# Sheet_1_2024-11-08.net
KiCad netlist of a schematic drawn in Altium Designer
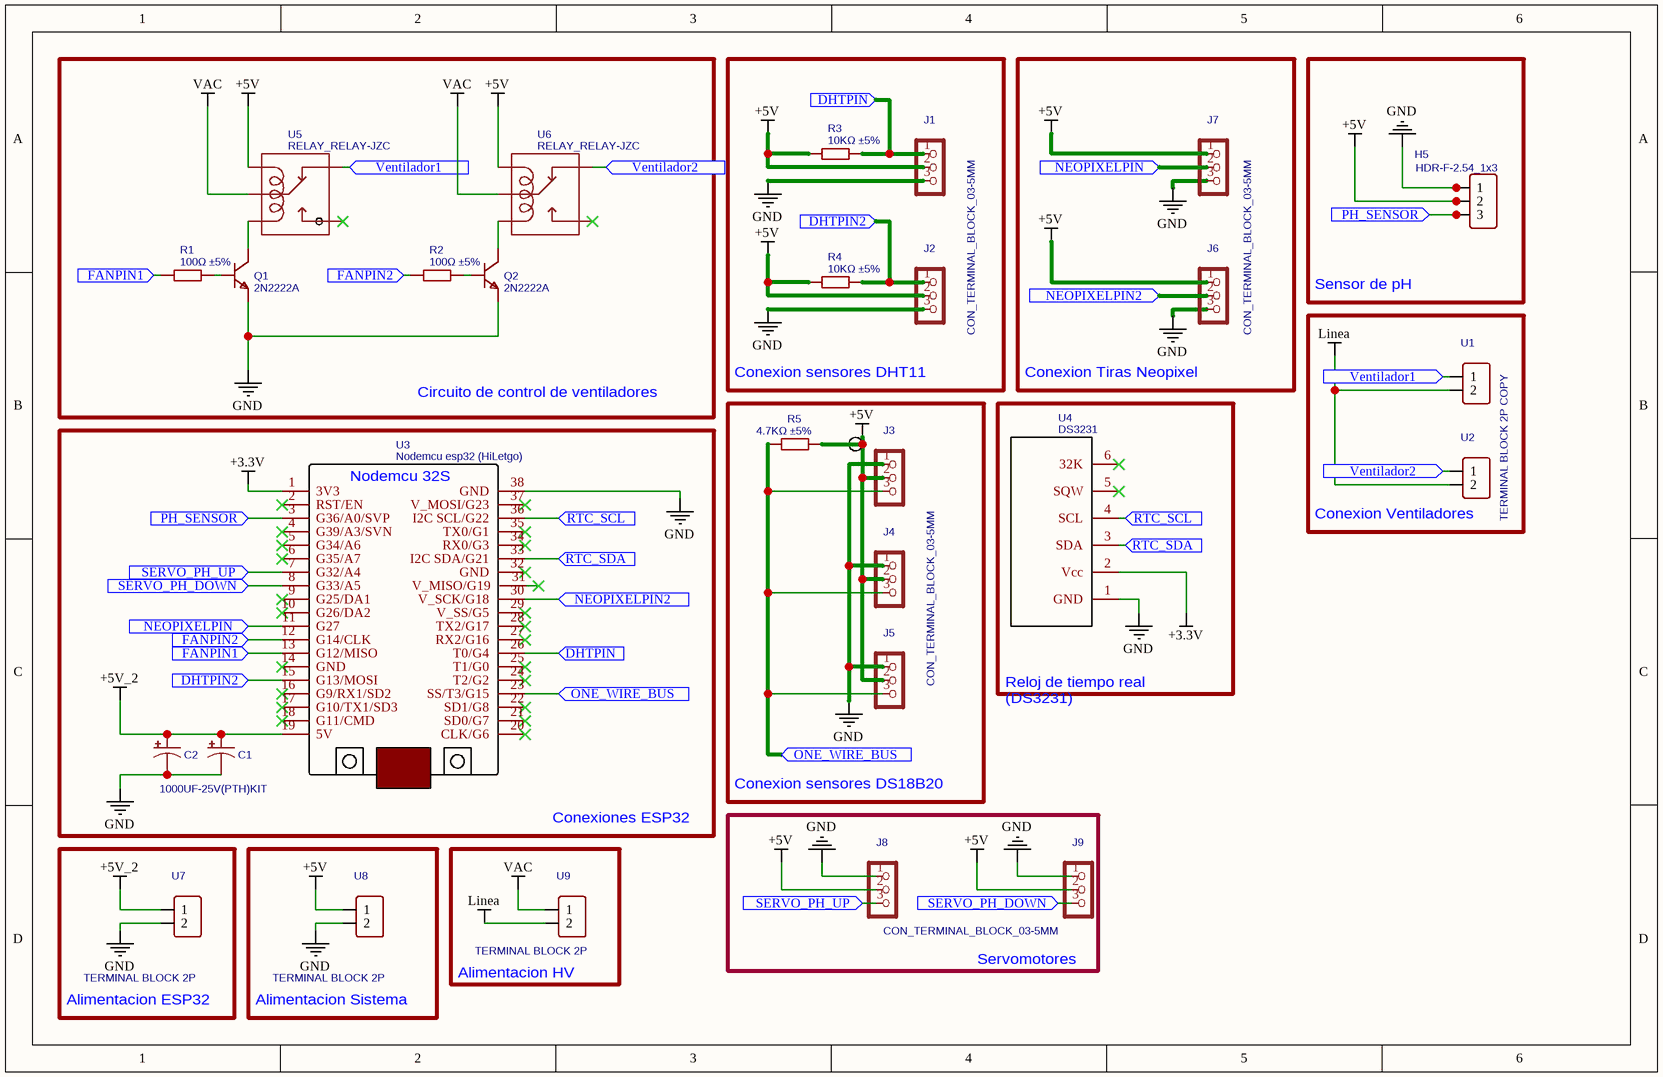
[diagram p0: Sheet_1_2024-11-08.schdoc]

(export (version "E")
  (design (tool "Eeschema 10.0.6"))
  (components
    (comp (ref "C1")
      (value "1000UF-25V(PTH)KIT")
      (description "CAP-08070")
      (fields (field (name "CONTRIBUTOR") "SparkFun"))
      (libsource (lib "altium-import") (part "root_0_1000UF-25V(PTH)KIT_"))
    )
    (comp (ref "C2")
      (value "1000UF-25V(PTH)KIT")
      (description "CAP-08070")
      (fields (field (name "CONTRIBUTOR") "SparkFun"))
      (libsource (lib "altium-import") (part "root_0_1000UF-25V(PTH)KIT_"))
    )
    (comp (ref "H5")
      (value "HDR-F-2.54_1x3")
      (fields (field (name "BOM_SUPPLIER PART") "C146690") (field (name "CONTRIBUTOR") "LCEDA_Lib"))
      (libsource (lib "altium-import") (part "root_0_HDR-F-2.54_1x3_"))
    )
    (comp (ref "J1")
      (value "CON_TERMINAL_BLOCK_03-5MM")
      (description "3 poles, wire to board connector")
      (fields (field (name "CONTRIBUTOR") "DangerousPrototype"))
      (libsource (lib "altium-import") (part "root_0_CON_TERMINAL_BLOCK_03-5MM_"))
    )
    (comp (ref "J2")
      (value "CON_TERMINAL_BLOCK_03-5MM")
      (description "3 poles, wire to board connector")
      (fields (field (name "CONTRIBUTOR") "DangerousPrototype"))
      (libsource (lib "altium-import") (part "root_0_CON_TERMINAL_BLOCK_03-5MM_"))
    )
    (comp (ref "J3")
      (value "CON_TERMINAL_BLOCK_03-5MM")
      (description "3 poles, wire to board connector")
      (fields (field (name "CONTRIBUTOR") "DangerousPrototype"))
      (libsource (lib "altium-import") (part "root_0_CON_TERMINAL_BLOCK_03-5MM_"))
    )
    (comp (ref "J4")
      (value "CON_TERMINAL_BLOCK_03-5MM")
      (description "3 poles, wire to board connector")
      (fields (field (name "CONTRIBUTOR") "DangerousPrototype"))
      (libsource (lib "altium-import") (part "root_0_CON_TERMINAL_BLOCK_03-5MM_"))
    )
    (comp (ref "J5")
      (value "CON_TERMINAL_BLOCK_03-5MM")
      (description "3 poles, wire to board connector")
      (fields (field (name "CONTRIBUTOR") "DangerousPrototype"))
      (libsource (lib "altium-import") (part "root_0_CON_TERMINAL_BLOCK_03-5MM_"))
    )
    (comp (ref "J6")
      (value "CON_TERMINAL_BLOCK_03-5MM")
      (description "3 poles, wire to board connector")
      (fields (field (name "CONTRIBUTOR") "DangerousPrototype"))
      (libsource (lib "altium-import") (part "root_0_CON_TERMINAL_BLOCK_03-5MM_"))
    )
    (comp (ref "J7")
      (value "CON_TERMINAL_BLOCK_03-5MM")
      (description "3 poles, wire to board connector")
      (fields (field (name "CONTRIBUTOR") "DangerousPrototype"))
      (libsource (lib "altium-import") (part "root_0_CON_TERMINAL_BLOCK_03-5MM_"))
    )
    (comp (ref "J8")
      (value "CON_TERMINAL_BLOCK_03-5MM")
      (description "3 poles, wire to board connector")
      (fields (field (name "CONTRIBUTOR") "DangerousPrototype"))
      (libsource (lib "altium-import") (part "root_0_CON_TERMINAL_BLOCK_03-5MM_"))
    )
    (comp (ref "J9")
      (value "CON_TERMINAL_BLOCK_03-5MM")
      (description "3 poles, wire to board connector")
      (fields (field (name "CONTRIBUTOR") "DangerousPrototype"))
      (libsource (lib "altium-import") (part "root_0_CON_TERMINAL_BLOCK_03-5MM_"))
    )
    (comp (ref "Q1")
      (value "2N2222A")
      (fields (field (name "BOM_SUPPLIER PART") "C358533") (field (name "CONTRIBUTOR") "som3a elshayeb"))
      (libsource (lib "altium-import") (part "root_0_2N2222A_"))
    )
    (comp (ref "Q2")
      (value "2N2222A")
      (fields (field (name "BOM_SUPPLIER PART") "C358533") (field (name "CONTRIBUTOR") "som3a elshayeb"))
      (libsource (lib "altium-import") (part "root_0_2N2222A_"))
    )
    (comp (ref "R1")
      (value "100Ω ±5%")
      (fields
        (field (name "BOM_SUPPLIER PART") "C123392")
        (field (name "BOM_MANUFACTURER PART") "MF58 103J3470")
        (field (name "CONTRIBUTOR") "Evgeniy_ANP")
      )
      (libsource (lib "altium-import") (part "root_0_100Ω ±5%_"))
    )
    (comp (ref "R2")
      (value "100Ω ±5%")
      (fields
        (field (name "BOM_SUPPLIER PART") "C123392")
        (field (name "BOM_MANUFACTURER PART") "MF58 103J3470")
        (field (name "CONTRIBUTOR") "Evgeniy_ANP")
      )
      (libsource (lib "altium-import") (part "root_0_100Ω ±5%_"))
    )
    (comp (ref "R3")
      (value "10KΩ ±5%")
      (fields
        (field (name "BOM_SUPPLIER PART") "C123392")
        (field (name "BOM_MANUFACTURER PART") "MF58 103J3470")
        (field (name "CONTRIBUTOR") "Evgeniy_ANP")
      )
      (libsource (lib "altium-import") (part "root_0_10KΩ ±5%_"))
    )
    (comp (ref "R4")
      (value "10KΩ ±5%")
      (fields
        (field (name "BOM_SUPPLIER PART") "C123392")
        (field (name "BOM_MANUFACTURER PART") "MF58 103J3470")
        (field (name "CONTRIBUTOR") "Evgeniy_ANP")
      )
      (libsource (lib "altium-import") (part "root_0_10KΩ ±5%_"))
    )
    (comp (ref "R5")
      (value "4.7KΩ ±5%")
      (fields
        (field (name "BOM_SUPPLIER PART") "C123392")
        (field (name "BOM_MANUFACTURER PART") "MF58 103J3470")
        (field (name "CONTRIBUTOR") "Evgeniy_ANP")
      )
      (libsource (lib "altium-import") (part "root_0_4.7KΩ ±5%_"))
    )
    (comp (ref "U1")
      (value "TERMINAL BLOCK 2P COPY")
      (fields (field (name "CONTRIBUTOR") "malakathushan"))
      (libsource (lib "altium-import") (part "root_0_TERMINAL BLOCK 2P COPY_"))
    )
    (comp (ref "U2")
      (value "TERMINAL BLOCK 2P COPY")
      (fields (field (name "CONTRIBUTOR") "malakathushan"))
      (libsource (lib "altium-import") (part "root_0_TERMINAL BLOCK 2P COPY_"))
    )
    (comp (ref "U3")
      (value "Nodemcu esp32 (HiLetgo)")
      (fields (field (name "CONTRIBUTOR") "j_dalrym2"))
      (libsource (lib "altium-import") (part "root_0_Nodemcu esp32 (HiLetgo)_"))
    )
    (comp (ref "U4")
      (value "DS3231")
      (fields (field (name "CONTRIBUTOR") "mwneal2014"))
      (libsource (lib "altium-import") (part "root_1_DS3231_"))
    )
    (comp (ref "U5")
      (value "RELAY_RELAY-JZC")
      (libsource (lib "altium-import") (part "root_0_RELAY_RELAY-JZC_"))
    )
    (comp (ref "U6")
      (value "RELAY_RELAY-JZC")
      (libsource (lib "altium-import") (part "root_0_RELAY_RELAY-JZC_"))
    )
    (comp (ref "U7")
      (value "TERMINAL BLOCK 2P")
      (fields (field (name "CONTRIBUTOR") "malakathushan"))
      (libsource (lib "altium-import") (part "root_0_TERMINAL BLOCK 2P_"))
    )
    (comp (ref "U8")
      (value "TERMINAL BLOCK 2P")
      (fields (field (name "CONTRIBUTOR") "malakathushan"))
      (libsource (lib "altium-import") (part "root_0_TERMINAL BLOCK 2P_"))
    )
    (comp (ref "U9")
      (value "TERMINAL BLOCK 2P")
      (fields (field (name "CONTRIBUTOR") "malakathushan"))
      (libsource (lib "altium-import") (part "root_0_TERMINAL BLOCK 2P_"))
    )
  )
  (nets
    (net (code "1") (name "+3.3V") (class "Default")
      (node (ref "U3") (pin "1") (pinfunction "3V3_1") (pintype "passive"))
      (node (ref "U4") (pin "2") (pinfunction "Vcc_2") (pintype "passive"))
    )
    (net (code "2") (name "+5V") (class "Default")
      (node (ref "H5") (pin "2") (pinfunction "2_2") (pintype "passive"))
      (node (ref "J1") (pin "2") (pinfunction "2_2") (pintype "passive"))
      (node (ref "J2") (pin "2") (pinfunction "2_2") (pintype "passive"))
      (node (ref "J3") (pin "2") (pinfunction "2_2") (pintype "passive"))
      (node (ref "J4") (pin "2") (pinfunction "2_2") (pintype "passive"))
      (node (ref "J5") (pin "2") (pinfunction "2_2") (pintype "passive"))
      (node (ref "J6") (pin "1") (pinfunction "1_1") (pintype "passive"))
      (node (ref "J7") (pin "1") (pinfunction "1_1") (pintype "passive"))
      (node (ref "J8") (pin "2") (pinfunction "2_2") (pintype "passive"))
      (node (ref "J9") (pin "2") (pinfunction "2_2") (pintype "passive"))
      (node (ref "R3") (pin "1") (pinfunction "1_1") (pintype "passive"))
      (node (ref "R4") (pin "1") (pinfunction "1_1") (pintype "passive"))
      (node (ref "R5") (pin "2") (pinfunction "2_2") (pintype "passive"))
      (node (ref "U5") (pin "1") (pinfunction "COIL1_1") (pintype "passive"))
      (node (ref "U6") (pin "1") (pinfunction "COIL1_1") (pintype "passive"))
      (node (ref "U8") (pin "1") (pinfunction "1_1") (pintype "passive"))
    )
    (net (code "3") (name "+5V_2") (class "Default")
      (node (ref "C1") (pin "+") (pinfunction "+_+") (pintype "passive"))
      (node (ref "C2") (pin "+") (pinfunction "+_+") (pintype "passive"))
      (node (ref "U3") (pin "19") (pinfunction "5V_19") (pintype "passive"))
      (node (ref "U7") (pin "1") (pinfunction "1_1") (pintype "passive"))
    )
    (net (code "4") (name "/DHTPIN") (class "Default")
      (node (ref "J1") (pin "1") (pinfunction "1_1") (pintype "passive"))
      (node (ref "R3") (pin "2") (pinfunction "2_2") (pintype "passive"))
      (node (ref "U3") (pin "26") (pinfunction "T0/G4_26") (pintype "passive"))
    )
    (net (code "5") (name "/DHTPIN2") (class "Default")
      (node (ref "J2") (pin "1") (pinfunction "1_1") (pintype "passive"))
      (node (ref "R4") (pin "2") (pinfunction "2_2") (pintype "passive"))
      (node (ref "U3") (pin "15") (pinfunction "G13/MOSI_15") (pintype "passive"))
    )
    (net (code "6") (name "/FANPIN1") (class "Default")
      (node (ref "R1") (pin "1") (pinfunction "1_1") (pintype "passive"))
      (node (ref "U3") (pin "13") (pinfunction "G12/MISO_13") (pintype "passive"))
    )
    (net (code "7") (name "/FANPIN2") (class "Default")
      (node (ref "R2") (pin "1") (pinfunction "1_1") (pintype "passive"))
      (node (ref "U3") (pin "12") (pinfunction "G14/CLK_12") (pintype "passive"))
    )
    (net (code "8") (name "/NEOPIXELPIN") (class "Default")
      (node (ref "J7") (pin "2") (pinfunction "2_2") (pintype "passive"))
      (node (ref "U3") (pin "11") (pinfunction "G27_11") (pintype "passive"))
    )
    (net (code "9") (name "/NEOPIXELPIN2") (class "Default")
      (node (ref "J6") (pin "2") (pinfunction "2_2") (pintype "passive"))
      (node (ref "U3") (pin "30") (pinfunction "V_SCK/G18_30") (pintype "passive"))
    )
    (net (code "10") (name "/ONE_WIRE_BUS") (class "Default")
      (node (ref "J3") (pin "3") (pinfunction "3_3") (pintype "passive"))
      (node (ref "J4") (pin "3") (pinfunction "3_3") (pintype "passive"))
      (node (ref "J5") (pin "3") (pinfunction "3_3") (pintype "passive"))
      (node (ref "R5") (pin "1") (pinfunction "1_1") (pintype "passive"))
      (node (ref "U3") (pin "23") (pinfunction "SS/T3/G15_23") (pintype "passive"))
    )
    (net (code "11") (name "/PH_SENSOR") (class "Default")
      (node (ref "H5") (pin "3") (pinfunction "3_3") (pintype "passive"))
      (node (ref "U3") (pin "3") (pinfunction "G36/A0/SVP_3") (pintype "passive"))
    )
    (net (code "12") (name "/RTC_SCL") (class "Default")
      (node (ref "U3") (pin "36") (pinfunction "I2C_SCL/G22_36") (pintype "passive"))
      (node (ref "U4") (pin "4") (pinfunction "SCL_4") (pintype "passive"))
    )
    (net (code "13") (name "/RTC_SDA") (class "Default")
      (node (ref "U3") (pin "33") (pinfunction "I2C_SDA/G21_33") (pintype "passive"))
      (node (ref "U4") (pin "3") (pinfunction "SDA_3") (pintype "passive"))
    )
    (net (code "14") (name "/SERVO_PH_DOWN") (class "Default")
      (node (ref "J9") (pin "3") (pinfunction "3_3") (pintype "passive"))
      (node (ref "U3") (pin "8") (pinfunction "G33/A5_8") (pintype "passive"))
    )
    (net (code "15") (name "/SERVO_PH_UP") (class "Default")
      (node (ref "J8") (pin "3") (pinfunction "3_3") (pintype "passive"))
      (node (ref "U3") (pin "7") (pinfunction "G32/A4_7") (pintype "passive"))
    )
    (net (code "16") (name "/Ventilador1") (class "Default")
      (node (ref "U1") (pin "1") (pinfunction "1_1") (pintype "passive"))
      (node (ref "U5") (pin "14") (pinfunction "NC_14") (pintype "passive"))
    )
    (net (code "17") (name "/Ventilador2") (class "Default")
      (node (ref "U2") (pin "1") (pinfunction "1_1") (pintype "passive"))
      (node (ref "U6") (pin "14") (pinfunction "NC_14") (pintype "passive"))
    )
    (net (code "18") (name "GND") (class "Default")
      (node (ref "C1") (pin "-") (pinfunction "-_-") (pintype "passive"))
      (node (ref "C2") (pin "-") (pinfunction "-_-") (pintype "passive"))
      (node (ref "H5") (pin "1") (pinfunction "1_1") (pintype "passive"))
      (node (ref "J1") (pin "3") (pinfunction "3_3") (pintype "passive"))
      (node (ref "J2") (pin "3") (pinfunction "3_3") (pintype "passive"))
      (node (ref "J3") (pin "1") (pinfunction "1_1") (pintype "passive"))
      (node (ref "J4") (pin "1") (pinfunction "1_1") (pintype "passive"))
      (node (ref "J5") (pin "1") (pinfunction "1_1") (pintype "passive"))
      (node (ref "J6") (pin "3") (pinfunction "3_3") (pintype "passive"))
      (node (ref "J7") (pin "3") (pinfunction "3_3") (pintype "passive"))
      (node (ref "J8") (pin "1") (pinfunction "1_1") (pintype "passive"))
      (node (ref "J9") (pin "1") (pinfunction "1_1") (pintype "passive"))
      (node (ref "Q1") (pin "3") (pinfunction "E_3") (pintype "passive"))
      (node (ref "Q2") (pin "3") (pinfunction "E_3") (pintype "passive"))
      (node (ref "U3") (pin "38") (pinfunction "GND_38") (pintype "passive"))
      (node (ref "U4") (pin "1") (pinfunction "GND_1") (pintype "passive"))
      (node (ref "U7") (pin "2") (pinfunction "2_2") (pintype "passive"))
      (node (ref "U8") (pin "2") (pinfunction "2_2") (pintype "passive"))
    )
    (net (code "19") (name "Linea") (class "Default")
      (node (ref "U1") (pin "2") (pinfunction "2_2") (pintype "passive"))
      (node (ref "U2") (pin "2") (pinfunction "2_2") (pintype "passive"))
      (node (ref "U9") (pin "2") (pinfunction "2_2") (pintype "passive"))
    )
    (net (code "20") (name "Net-(Q1-B)") (class "Default")
      (node (ref "Q1") (pin "2") (pinfunction "B_2") (pintype "passive"))
      (node (ref "R1") (pin "2") (pinfunction "2_2") (pintype "passive"))
    )
    (net (code "21") (name "Net-(Q1-C)") (class "Default")
      (node (ref "Q1") (pin "1") (pinfunction "C_1") (pintype "passive"))
      (node (ref "U5") (pin "2") (pinfunction "COIL2_2") (pintype "passive"))
    )
    (net (code "22") (name "Net-(Q2-B)") (class "Default")
      (node (ref "Q2") (pin "2") (pinfunction "B_2") (pintype "passive"))
      (node (ref "R2") (pin "2") (pinfunction "2_2") (pintype "passive"))
    )
    (net (code "23") (name "Net-(Q2-C)") (class "Default")
      (node (ref "Q2") (pin "1") (pinfunction "C_1") (pintype "passive"))
      (node (ref "U6") (pin "2") (pinfunction "COIL2_2") (pintype "passive"))
    )
    (net (code "24") (name "VAC") (class "Default")
      (node (ref "U5") (pin "4") (pinfunction "MAIN_4") (pintype "passive"))
      (node (ref "U6") (pin "4") (pinfunction "MAIN_4") (pintype "passive"))
      (node (ref "U9") (pin "1") (pinfunction "1_1") (pintype "passive"))
    )
    (net (code "25") (name "unconnected-(U3-CLK{slash}G6-Pad20)") (class "Default")
      (node (ref "U3") (pin "20") (pinfunction "CLK/G6_20") (pintype "passive+no_connect"))
    )
    (net (code "26") (name "unconnected-(U3-G9{slash}RX1{slash}SD2-Pad16)") (class "Default")
      (node (ref "U3") (pin "16") (pinfunction "G9/RX1/SD2_16") (pintype "passive+no_connect"))
    )
    (net (code "27") (name "unconnected-(U3-G10{slash}TX1{slash}SD3-Pad17)") (class "Default")
      (node (ref "U3") (pin "17") (pinfunction "G10/TX1/SD3_17") (pintype "passive+no_connect"))
    )
    (net (code "28") (name "unconnected-(U3-G11{slash}CMD-Pad18)") (class "Default")
      (node (ref "U3") (pin "18") (pinfunction "G11/CMD_18") (pintype "passive+no_connect"))
    )
    (net (code "29") (name "unconnected-(U3-G25{slash}DA1-Pad9)") (class "Default")
      (node (ref "U3") (pin "9") (pinfunction "G25/DA1_9") (pintype "passive+no_connect"))
    )
    (net (code "30") (name "unconnected-(U3-G26{slash}DA2-Pad10)") (class "Default")
      (node (ref "U3") (pin "10") (pinfunction "G26/DA2_10") (pintype "passive+no_connect"))
    )
    (net (code "31") (name "unconnected-(U3-G34{slash}A6-Pad5)") (class "Default")
      (node (ref "U3") (pin "5") (pinfunction "G34/A6_5") (pintype "passive+no_connect"))
    )
    (net (code "32") (name "unconnected-(U3-G35{slash}A7-Pad6)") (class "Default")
      (node (ref "U3") (pin "6") (pinfunction "G35/A7_6") (pintype "passive+no_connect"))
    )
    (net (code "33") (name "unconnected-(U3-G39{slash}A3{slash}SVN-Pad4)") (class "Default")
      (node (ref "U3") (pin "4") (pinfunction "G39/A3/SVN_4") (pintype "passive+no_connect"))
    )
    (net (code "34") (name "unconnected-(U3-GND-Pad14)") (class "Default")
      (node (ref "U3") (pin "14") (pinfunction "GND_14") (pintype "passive+no_connect"))
    )
    (net (code "35") (name "unconnected-(U3-GND-Pad32)") (class "Default")
      (node (ref "U3") (pin "32") (pinfunction "GND_32") (pintype "passive+no_connect"))
    )
    (net (code "36") (name "unconnected-(U3-RST{slash}EN-Pad2)") (class "Default")
      (node (ref "U3") (pin "2") (pinfunction "RST/EN_2") (pintype "passive+no_connect"))
    )
    (net (code "37") (name "unconnected-(U3-RX0{slash}G3-Pad34)") (class "Default")
      (node (ref "U3") (pin "34") (pinfunction "RX0/G3_34") (pintype "passive+no_connect"))
    )
    (net (code "38") (name "unconnected-(U3-RX2{slash}G16-Pad27)") (class "Default")
      (node (ref "U3") (pin "27") (pinfunction "RX2/G16_27") (pintype "passive+no_connect"))
    )
    (net (code "39") (name "unconnected-(U3-SD0{slash}G7-Pad21)") (class "Default")
      (node (ref "U3") (pin "21") (pinfunction "SD0/G7_21") (pintype "passive+no_connect"))
    )
    (net (code "40") (name "unconnected-(U3-SD1{slash}G8-Pad22)") (class "Default")
      (node (ref "U3") (pin "22") (pinfunction "SD1/G8_22") (pintype "passive+no_connect"))
    )
    (net (code "41") (name "unconnected-(U3-T1{slash}G0-Pad25)") (class "Default")
      (node (ref "U3") (pin "25") (pinfunction "T1/G0_25") (pintype "passive+no_connect"))
    )
    (net (code "42") (name "unconnected-(U3-T2{slash}G2-Pad24)") (class "Default")
      (node (ref "U3") (pin "24") (pinfunction "T2/G2_24") (pintype "passive+no_connect"))
    )
    (net (code "43") (name "unconnected-(U3-TX0{slash}G1-Pad35)") (class "Default")
      (node (ref "U3") (pin "35") (pinfunction "TX0/G1_35") (pintype "passive+no_connect"))
    )
    (net (code "44") (name "unconnected-(U3-TX2{slash}G17-Pad28)") (class "Default")
      (node (ref "U3") (pin "28") (pinfunction "TX2/G17_28") (pintype "passive+no_connect"))
    )
    (net (code "45") (name "unconnected-(U3-V_MISO{slash}G19-Pad31)") (class "Default")
      (node (ref "U3") (pin "31") (pinfunction "V_MISO/G19_31") (pintype "passive+no_connect"))
    )
    (net (code "46") (name "unconnected-(U3-V_MOSI{slash}G23-Pad37)") (class "Default")
      (node (ref "U3") (pin "37") (pinfunction "V_MOSI/G23_37") (pintype "passive+no_connect"))
    )
    (net (code "47") (name "unconnected-(U3-V_SS{slash}G5-Pad29)") (class "Default")
      (node (ref "U3") (pin "29") (pinfunction "V_SS/G5_29") (pintype "passive+no_connect"))
    )
    (net (code "48") (name "unconnected-(U4-32K-Pad6)") (class "Default")
      (node (ref "U4") (pin "6") (pinfunction "32K_6") (pintype "passive+no_connect"))
    )
    (net (code "49") (name "unconnected-(U4-SQW-Pad5)") (class "Default")
      (node (ref "U4") (pin "5") (pinfunction "SQW_5") (pintype "passive+no_connect"))
    )
    (net (code "50") (name "unconnected-(U5-NO-Pad3)") (class "Default")
      (node (ref "U5") (pin "3") (pinfunction "NO_3") (pintype "passive+no_connect"))
    )
    (net (code "51") (name "unconnected-(U6-NO-Pad3)") (class "Default")
      (node (ref "U6") (pin "3") (pinfunction "NO_3") (pintype "passive+no_connect"))
    )
  )
)
